# 18V5_efuse.net
KiCad netlist of a schematic drawn in Altium Designer
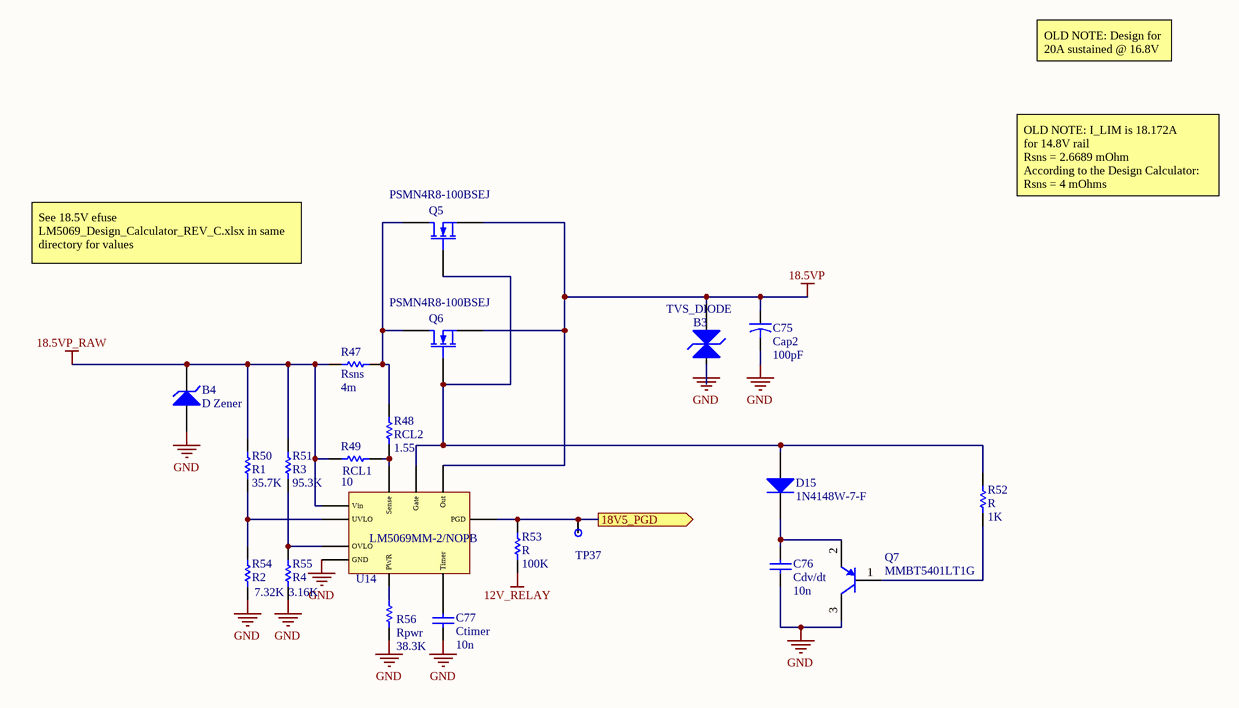
[diagram p0: 18V5_efuse.SchDoc]

(export (version "E")
  (design (tool "Eeschema 10.0.6"))
  (components
    (comp (ref "B3")
      (value "TVS_DIODE")
      (footprint "SMBJ54A-13-F")
      (description "TVS Diode")
      (fields (field (name "PUBLISHER") "Altium Limited"))
      (libsource (lib "RSX_Diodes") (part "TVS_DIODE"))
    )
    (comp (ref "B4")
      (value "D Zener")
      (footprint "DIODE-0.7")
      (description "Zener Diode")
      (fields (field (name "PUBLISHER") "Altium Limited"))
      (libsource (lib "Miscellaneous Devices") (part "D Zener"))
    )
    (comp (ref "C75")
      (value "Cap2")
      (footprint "CAPR5-4X5")
      (description "Capacitor")
      (fields (field (name "ALTIUM_VALUE") "100pF") (field (name "PUBLISHER") "Altium Limited"))
      (libsource (lib "Miscellaneous Devices") (part "Cap2"))
    )
    (comp (ref "C76")
      (value "Cdv/dt")
      (footprint "RAD-0.3")
      (description "Capacitor")
      (fields (field (name "ALTIUM_VALUE") "10n") (field (name "PUBLISHER") "Altium Limited"))
      (libsource (lib "Miscellaneous Devices") (part "Cap"))
    )
    (comp (ref "C77")
      (value "Ctimer")
      (footprint "RAD-0.3")
      (description "Capacitor")
      (fields (field (name "ALTIUM_VALUE") "10n") (field (name "PUBLISHER") "Altium Limited"))
      (libsource (lib "Miscellaneous Devices") (part "Cap"))
    )
    (comp (ref "D15")
      (value "1N4148W-7-F")
      (footprint "DIOD-SOD123-2_V")
      (description "Fast Switching Diode, 100 V, 0.15 A, -65 to 150 degC, 2-Pin?SOD123, RoHS, Tape and Reel")
      (fields (field (name "MANUFACTURER") "DiodesIncorporated"))
      (libsource (lib "Altium Content Vault") (part "D-AK-2"))
    )
    (comp (ref "Q5")
      (value "PSMN4R8-100BSEJ")
      (footprint "DPAK254P1420X457-3N")
      (description "N-Channel MOSFET")
      (fields (field (name "PUBLISHER") "Altium Limited"))
      (libsource (lib "RSX_ICs") (part "PSMN4R8-100BSEJ"))
    )
    (comp (ref "Q6")
      (value "PSMN4R8-100BSEJ")
      (footprint "DPAK254P1420X457-3N")
      (description "N-Channel MOSFET")
      (fields (field (name "PUBLISHER") "Altium Limited"))
      (libsource (lib "RSX_ICs") (part "PSMN4R8-100BSEJ"))
    )
    (comp (ref "Q7")
      (value "MMBT5401LT1G")
      (footprint "ONSC-SOT-23-3-318-08_V")
      (description "High Voltage Transistor, PNP Silicon, 3-Pin SOT-23, Pb-Free, Tape and Reel")
      (fields (field (name "MANUFACTURER") "On Semiconductor"))
      (libsource (lib "Altium Content Vault") (part "ONSC-PNP-B1E2C3-3"))
    )
    (comp (ref "R47")
      (value "Rsns")
      (footprint "RESC1608X06N_0603")
      (description "Resistor")
      (fields (field (name "ALTIUM_VALUE") "4m") (field (name "PUBLISHER") "Altium Limited"))
      (libsource (lib "RSX_Resistors") (part "Res1"))
    )
    (comp (ref "R48")
      (value "RCL2")
      (footprint "RESC1608X06N_0603")
      (description "Resistor")
      (fields (field (name "ALTIUM_VALUE") "1.55") (field (name "PUBLISHER") "Altium Limited"))
      (libsource (lib "RSX_Resistors") (part "Res1"))
    )
    (comp (ref "R49")
      (value "RCL1")
      (footprint "RESC1608X06N_0603")
      (description "Resistor")
      (fields (field (name "ALTIUM_VALUE") "10") (field (name "PUBLISHER") "Altium Limited"))
      (libsource (lib "RSX_Resistors") (part "Res1"))
    )
    (comp (ref "R50")
      (value "R1")
      (footprint "RESC1608X06N_0603")
      (description "Resistor")
      (fields (field (name "ALTIUM_VALUE") "35.7K") (field (name "PUBLISHER") "Altium Limited"))
      (libsource (lib "RSX_Resistors") (part "Res1"))
    )
    (comp (ref "R51")
      (value "R3")
      (footprint "RESC1608X06N_0603")
      (description "Resistor")
      (fields (field (name "ALTIUM_VALUE") "95.3K") (field (name "PUBLISHER") "Altium Limited"))
      (libsource (lib "RSX_Resistors") (part "Res1"))
    )
    (comp (ref "R52")
      (value "R")
      (footprint "RESC1608X06N_0603")
      (description "Resistor")
      (fields (field (name "ALTIUM_VALUE") "1K") (field (name "PUBLISHER") "Altium Limited"))
      (libsource (lib "RSX_Resistors") (part "Res1"))
    )
    (comp (ref "R53")
      (value "R")
      (footprint "RESC1608X06N_0603")
      (description "Resistor")
      (fields (field (name "ALTIUM_VALUE") "100K") (field (name "PUBLISHER") "Altium Limited"))
      (libsource (lib "RSX_Resistors") (part "Res1"))
    )
    (comp (ref "R54")
      (value "R2")
      (footprint "RESC1608X06N_0603")
      (description "Resistor")
      (fields (field (name "ALTIUM_VALUE") "7.32K") (field (name "PUBLISHER") "Altium Limited"))
      (libsource (lib "RSX_Resistors") (part "Res1"))
    )
    (comp (ref "R55")
      (value "R4")
      (footprint "RESC1608X06N_0603")
      (description "Resistor")
      (fields (field (name "ALTIUM_VALUE") "3.16K") (field (name "PUBLISHER") "Altium Limited"))
      (libsource (lib "RSX_Resistors") (part "Res1"))
    )
    (comp (ref "R56")
      (value "Rpwr")
      (footprint "RESC1608X06N_0603")
      (description "Resistor")
      (fields (field (name "ALTIUM_VALUE") "38.3K") (field (name "PUBLISHER") "Altium Limited"))
      (libsource (lib "RSX_Resistors") (part "Res1"))
    )
    (comp (ref "TP37")
      (value "TestPt")
      (footprint "50_MIL_PAD")
      (libsource (lib "RSX_Test_Points") (part "TestPt"))
    )
    (comp (ref "U14")
      (value "LM5069MM-2/NOPB")
      (footprint "TSSOP50P490X110-10N")
      (description "Hot Swap Controller 1-CH 80V N-Channel Positive High Voltage 10-Pin VSSOP T/R")
      (libsource (lib "RSX_ICs") (part "LM5069MM-2/NOPB"))
    )
  )
  (nets
    (net (code "1") (name "/18V5_PGD") (class "Default")
      (node (ref "R53") (pin "2") (pinfunction "2_2") (pintype "passive"))
      (node (ref "TP37") (pin "1") (pinfunction "1_1") (pintype "passive"))
      (node (ref "U14") (pin "8") (pinfunction "PGD_8") (pintype "passive"))
    )
    (net (code "2") (name "12V_RELAY") (class "Default")
      (node (ref "R53") (pin "1") (pinfunction "1_1") (pintype "passive"))
    )
    (net (code "3") (name "18.5VP") (class "Default")
      (node (ref "B3") (pin "2") (pinfunction "K_2") (pintype "passive"))
      (node (ref "C75") (pin "1") (pinfunction "1_1") (pintype "passive"))
      (node (ref "Q5") (pin "3") (pinfunction "S_3") (pintype "passive"))
      (node (ref "Q6") (pin "3") (pinfunction "S_3") (pintype "passive"))
      (node (ref "U14") (pin "9") (pinfunction "Out_9") (pintype "passive"))
    )
    (net (code "4") (name "18.5VP_RAW") (class "Default")
      (node (ref "B4") (pin "2") (pinfunction "K_2") (pintype "passive"))
      (node (ref "R47") (pin "1") (pinfunction "1_1") (pintype "passive"))
      (node (ref "R49") (pin "1") (pinfunction "1_1") (pintype "passive"))
      (node (ref "R50") (pin "2") (pinfunction "2_2") (pintype "passive"))
      (node (ref "R51") (pin "2") (pinfunction "2_2") (pintype "passive"))
      (node (ref "U14") (pin "2") (pinfunction "Vin_2") (pintype "passive"))
    )
    (net (code "5") (name "GND") (class "Default")
      (node (ref "B3") (pin "1") (pinfunction "A_1") (pintype "passive"))
      (node (ref "B4") (pin "1") (pinfunction "A_1") (pintype "passive"))
      (node (ref "C75") (pin "2") (pinfunction "2_2") (pintype "passive"))
      (node (ref "C76") (pin "2") (pinfunction "2_2") (pintype "passive"))
      (node (ref "C77") (pin "1") (pinfunction "1_1") (pintype "passive"))
      (node (ref "Q7") (pin "3") (pinfunction "C_3") (pintype "passive"))
      (node (ref "R54") (pin "1") (pinfunction "1_1") (pintype "passive"))
      (node (ref "R55") (pin "1") (pinfunction "1_1") (pintype "passive"))
      (node (ref "R56") (pin "1") (pinfunction "1_1") (pintype "passive"))
      (node (ref "U14") (pin "5") (pinfunction "GND_5") (pintype "passive"))
    )
    (net (code "6") (name "Net-(D15-A)") (class "Default")
      (node (ref "D15") (pin "1") (pinfunction "A_1") (pintype "passive"))
      (node (ref "Q5") (pin "1") (pinfunction "G_1") (pintype "passive"))
      (node (ref "Q6") (pin "1") (pinfunction "G_1") (pintype "passive"))
      (node (ref "R52") (pin "2") (pinfunction "2_2") (pintype "passive"))
      (node (ref "U14") (pin "10") (pinfunction "Gate_10") (pintype "passive"))
    )
    (net (code "7") (name "Net-(D15-K)") (class "Default")
      (node (ref "C76") (pin "1") (pinfunction "1_1") (pintype "passive"))
      (node (ref "D15") (pin "2") (pinfunction "K_2") (pintype "passive"))
      (node (ref "Q7") (pin "2") (pinfunction "E_2") (pintype "passive"))
    )
    (net (code "8") (name "Net-(Q5-D)") (class "Default")
      (node (ref "Q5") (pin "2") (pinfunction "D_2") (pintype "passive"))
      (node (ref "Q6") (pin "2") (pinfunction "D_2") (pintype "passive"))
      (node (ref "R47") (pin "2") (pinfunction "2_2") (pintype "passive"))
      (node (ref "R48") (pin "2") (pinfunction "2_2") (pintype "passive"))
    )
    (net (code "9") (name "Net-(Q7-B)") (class "Default")
      (node (ref "Q7") (pin "1") (pinfunction "B_1") (pintype "passive"))
      (node (ref "R52") (pin "1") (pinfunction "1_1") (pintype "passive"))
    )
    (net (code "10") (name "Net-(U14-OVLO)") (class "Default")
      (node (ref "R51") (pin "1") (pinfunction "1_1") (pintype "passive"))
      (node (ref "R55") (pin "2") (pinfunction "2_2") (pintype "passive"))
      (node (ref "U14") (pin "4") (pinfunction "OVLO_4") (pintype "passive"))
    )
    (net (code "11") (name "Net-(U14-PWR)") (class "Default")
      (node (ref "R56") (pin "2") (pinfunction "2_2") (pintype "passive"))
      (node (ref "U14") (pin "7") (pinfunction "PWR_7") (pintype "passive"))
    )
    (net (code "12") (name "Net-(U14-Sense)") (class "Default")
      (node (ref "R48") (pin "1") (pinfunction "1_1") (pintype "passive"))
      (node (ref "R49") (pin "2") (pinfunction "2_2") (pintype "passive"))
      (node (ref "U14") (pin "1") (pinfunction "Sense_1") (pintype "passive"))
    )
    (net (code "13") (name "Net-(U14-Timer)") (class "Default")
      (node (ref "C77") (pin "2") (pinfunction "2_2") (pintype "passive"))
      (node (ref "U14") (pin "6") (pinfunction "Timer_6") (pintype "passive"))
    )
    (net (code "14") (name "Net-(U14-UVLO)") (class "Default")
      (node (ref "R50") (pin "1") (pinfunction "1_1") (pintype "passive"))
      (node (ref "R54") (pin "2") (pinfunction "2_2") (pintype "passive"))
      (node (ref "U14") (pin "3") (pinfunction "UVLO_3") (pintype "passive"))
    )
  )
)
